# warm_floor.net
KiCad netlist of a schematic drawn in EAGLE
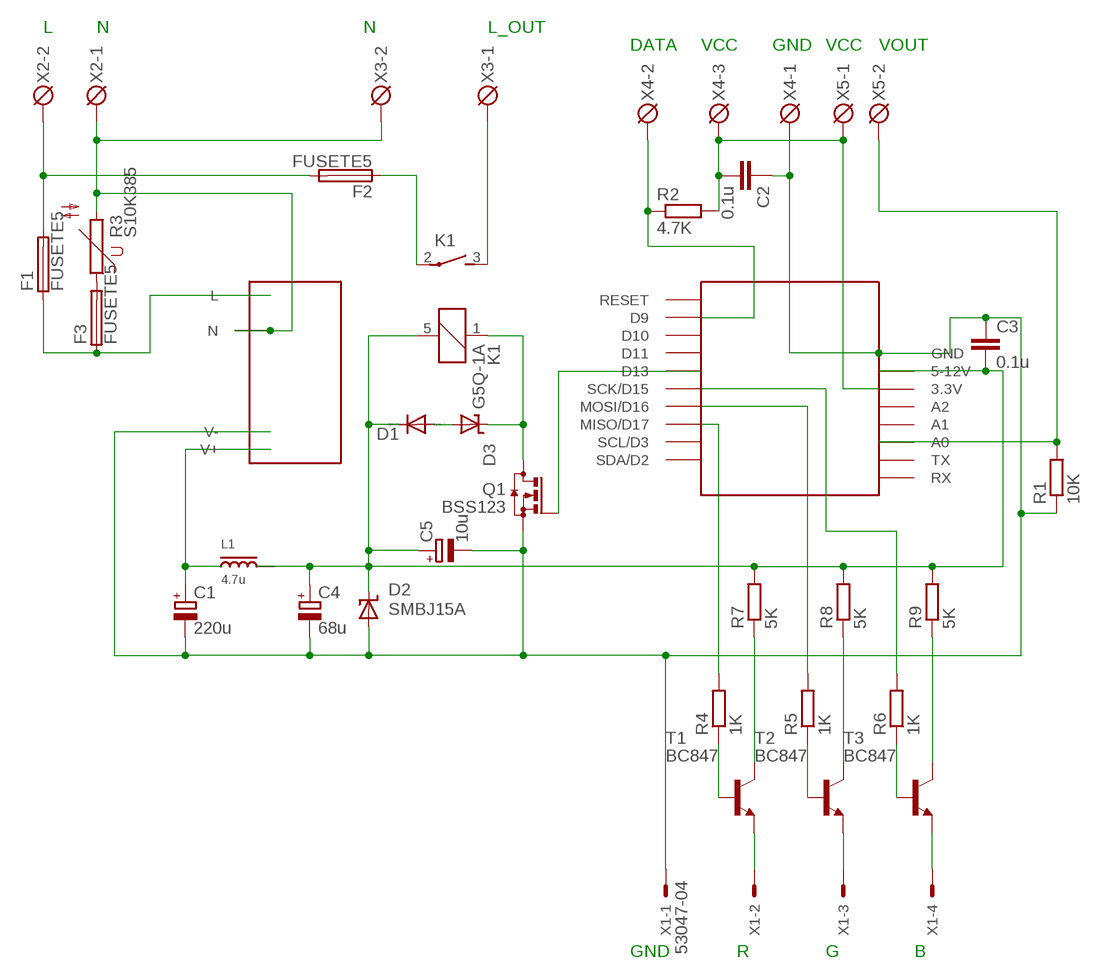
[diagram p0: schematic, sheet 1]

(export (version "E")
  (design (tool "Eeschema 10.0.6"))
  (components
    (comp (ref "C1")
      (value "220u")
      (footprint "eagle-import:E2,5-6")
      (libsource (lib "eagle-import") (part "CPOL-EUE2.5-6"))
    )
    (comp (ref "C2")
      (value "0.1u")
      (footprint "eagle-import:C0805")
      (libsource (lib "eagle-import") (part "C-EUC0805"))
    )
    (comp (ref "C3")
      (value "0.1u")
      (footprint "eagle-import:C0805")
      (libsource (lib "eagle-import") (part "C-EUC0805"))
    )
    (comp (ref "C4")
      (value "68u")
      (footprint "eagle-import:E2,5-7")
      (libsource (lib "eagle-import") (part "CPOL-EUE2.5-7"))
    )
    (comp (ref "C5")
      (value "10u")
      (footprint "eagle-import:E2,5-6")
      (libsource (lib "eagle-import") (part "CPOL-EUE2.5-6"))
    )
    (comp (ref "D1")
      (value "DIODE-SOD123")
      (footprint "eagle-import:SOD123")
      (libsource (lib "eagle-import") (part "DIODE-SOD123"))
    )
    (comp (ref "D2")
      (value "SMBJ15A")
      (footprint "eagle-import:SMBJ")
      (libsource (lib "eagle-import") (part "SUPPRESSOR-SMBJ"))
    )
    (comp (ref "D3")
      (value "SUPPRESSOR-SMBJ")
      (footprint "eagle-import:SMBJ")
      (libsource (lib "eagle-import") (part "SUPPRESSOR-SMBJ"))
    )
    (comp (ref "F1")
      (value "FUSETE5")
      (footprint "eagle-import:TE5")
      (libsource (lib "eagle-import") (part "FUSETE5"))
    )
    (comp (ref "F2")
      (value "FUSETE5")
      (footprint "eagle-import:TE5")
      (libsource (lib "eagle-import") (part "FUSETE5"))
    )
    (comp (ref "F3")
      (value "FUSETE5")
      (footprint "eagle-import:TE5")
      (libsource (lib "eagle-import") (part "FUSETE5"))
    )
    (comp (ref "K1")
      (value "G5Q-1A")
      (footprint "eagle-import:G5Q-1A")
      (libsource (lib "eagle-import") (part "G5Q-1A"))
    )
    (comp (ref "L1")
      (value "4.7u")
      (footprint "eagle-import:LQH43")
      (libsource (lib "eagle-import") (part "LQH43"))
    )
    (comp (ref "Q1")
      (value "BSS123")
      (footprint "eagle-import:SOT23")
      (libsource (lib "eagle-import") (part "BSS123"))
    )
    (comp (ref "R1")
      (value "10K")
      (footprint "eagle-import:R0805")
      (libsource (lib "eagle-import") (part "R-EU_R0805"))
    )
    (comp (ref "R2")
      (value "4.7K")
      (footprint "eagle-import:R0805")
      (libsource (lib "eagle-import") (part "R-EU_R0805"))
    )
    (comp (ref "R3")
      (value "S10K385")
      (footprint "eagle-import:S10K385")
      (libsource (lib "eagle-import") (part "S10K385"))
    )
    (comp (ref "R4")
      (value "1K")
      (footprint "eagle-import:R0805")
      (libsource (lib "eagle-import") (part "resistor_348_R-EU_R0805"))
    )
    (comp (ref "R5")
      (value "1K")
      (footprint "eagle-import:R0805")
      (libsource (lib "eagle-import") (part "resistor_348_R-EU_R0805"))
    )
    (comp (ref "R6")
      (value "1K")
      (footprint "eagle-import:R0805")
      (libsource (lib "eagle-import") (part "resistor_348_R-EU_R0805"))
    )
    (comp (ref "R7")
      (value "5K")
      (footprint "eagle-import:R0805")
      (libsource (lib "eagle-import") (part "resistor_348_R-EU_R0805"))
    )
    (comp (ref "R8")
      (value "5K")
      (footprint "eagle-import:R0805")
      (libsource (lib "eagle-import") (part "resistor_348_R-EU_R0805"))
    )
    (comp (ref "R9")
      (value "5K")
      (footprint "eagle-import:R0805")
      (libsource (lib "eagle-import") (part "resistor_348_R-EU_R0805"))
    )
    (comp (ref "T1")
      (value "BC847")
      (footprint "eagle-import:SOT23")
      (libsource (lib "eagle-import") (part "BC847"))
    )
    (comp (ref "T2")
      (value "BC847")
      (footprint "eagle-import:SOT23")
      (libsource (lib "eagle-import") (part "BC847"))
    )
    (comp (ref "T3")
      (value "BC847")
      (footprint "eagle-import:SOT23")
      (libsource (lib "eagle-import") (part "BC847"))
    )
    (comp (ref "U$1")
      (value "SMARTBRICK")
      (footprint "eagle-import:SMARTBRICK")
      (libsource (lib "eagle-import") (part "SMARTBRICK"))
    )
    (comp (ref "U$2")
      (value "NA01/02-T2SXX")
      (footprint "eagle-import:NA01_02-T2SXX")
      (libsource (lib "eagle-import") (part "NA01/02-T2SXX"))
    )
    (comp (ref "X1")
      (value "53047-04")
      (footprint "eagle-import:53047-04")
      (fields (field (name "MF") "WALDOM/MOLEX") (field (name "MPN") "53047-0410"))
      (libsource (lib "eagle-import") (part "53?-04047"))
    )
    (comp (ref "X2")
      (value "DG3XX-025.0")
      (footprint "eagle-import:DG300-5.0-02P")
      (libsource (lib "eagle-import") (part "DG3XX-025.0"))
    )
    (comp (ref "X3")
      (value "DG3XX-025.0")
      (footprint "eagle-import:DG300-5.0-02P")
      (libsource (lib "eagle-import") (part "DG3XX-025.0"))
    )
    (comp (ref "X4")
      (value "DG3XX-03-3.5")
      (footprint "eagle-import:DG350-3.5-03P")
      (libsource (lib "eagle-import") (part "DG3XX-03-3.5"))
    )
    (comp (ref "X5")
      (value "DG3XX-02-3.5")
      (footprint "eagle-import:DG350-3.5-02P")
      (libsource (lib "eagle-import") (part "DG3XX-02-3.5"))
    )
  )
  (nets
    (net (code "1") (name "Net-(C1-Pad+)") (class "Default")
      (node (ref "C1") (pin "+") (pinfunction "+_+") (pintype "passive"))
      (node (ref "L1") (pin "P$1") (pinfunction "P$1_P$1") (pintype "bidirectional"))
      (node (ref "U$2") (pin "V+") (pinfunction "V+_V+") (pintype "output"))
    )
    (net (code "2") (name "Net-(D1-PadA)") (class "Default")
      (node (ref "D1") (pin "A") (pinfunction "A_A") (pintype "passive"))
      (node (ref "D3") (pin "A") (pinfunction "A_A") (pintype "passive"))
    )
    (net (code "3") (name "Net-(F1-Pad1)") (class "Default")
      (node (ref "F1") (pin "1") (pinfunction "1_1") (pintype "passive"))
      (node (ref "F3") (pin "1") (pinfunction "1_1") (pintype "passive"))
      (node (ref "U$2") (pin "L") (pinfunction "L_L") (pintype "input"))
    )
    (net (code "4") (name "Net-(F3-Pad2)") (class "Default")
      (node (ref "F3") (pin "2") (pinfunction "2_2") (pintype "passive"))
      (node (ref "R3") (pin "1") (pinfunction "1_1") (pintype "passive"))
    )
    (net (code "5") (name "Net-(K1A-2)") (class "Default")
      (node (ref "C3") (pin "2") (pinfunction "2_2") (pintype "passive"))
      (node (ref "C4") (pin "+") (pinfunction "+_+") (pintype "passive"))
      (node (ref "C5") (pin "+") (pinfunction "+_+") (pintype "passive"))
      (node (ref "D1") (pin "C") (pinfunction "C_C") (pintype "passive"))
      (node (ref "D2") (pin "C") (pinfunction "C_C") (pintype "passive"))
      (node (ref "K1") (pin "5") (pinfunction "2_5") (pintype "passive"))
      (node (ref "L1") (pin "P$2") (pinfunction "P$2_P$2") (pintype "bidirectional"))
      (node (ref "R7") (pin "2") (pinfunction "2_2") (pintype "passive"))
      (node (ref "R8") (pin "2") (pinfunction "2_2") (pintype "passive"))
      (node (ref "R9") (pin "2") (pinfunction "2_2") (pintype "passive"))
      (node (ref "U$1") (pin "VIN") (pinfunction "5-12V_VIN") (pintype "input"))
    )
    (net (code "6") (name "Net-(K1B-P)") (class "Default")
      (node (ref "F2") (pin "1") (pinfunction "1_1") (pintype "passive"))
      (node (ref "K1") (pin "2") (pinfunction "P_2") (pintype "passive"))
    )
    (net (code "7") (name "Net-(K1B-S)") (class "Default")
      (node (ref "K1") (pin "3") (pinfunction "S_3") (pintype "passive"))
      (node (ref "X3") (pin "1") (pinfunction "KL_1") (pintype "passive"))
    )
    (net (code "8") (name "Net-(Q1-D)") (class "Default")
      (node (ref "D3") (pin "C") (pinfunction "C_C") (pintype "passive"))
      (node (ref "K1") (pin "1") (pinfunction "1_1") (pintype "passive"))
      (node (ref "Q1") (pin "3") (pinfunction "D_3") (pintype "passive"))
    )
    (net (code "9") (name "Net-(Q1-G)") (class "Default")
      (node (ref "Q1") (pin "1") (pinfunction "G_1") (pintype "passive"))
      (node (ref "U$1") (pin "D13") (pinfunction "D13_D13") (pintype "bidirectional"))
    )
    (net (code "10") (name "Net-(Q1-S)") (class "Default")
      (node (ref "C1") (pin "-") (pinfunction "-_-") (pintype "passive"))
      (node (ref "C2") (pin "1") (pinfunction "1_1") (pintype "passive"))
      (node (ref "C3") (pin "1") (pinfunction "1_1") (pintype "passive"))
      (node (ref "C4") (pin "-") (pinfunction "-_-") (pintype "passive"))
      (node (ref "C5") (pin "-") (pinfunction "-_-") (pintype "passive"))
      (node (ref "D2") (pin "A") (pinfunction "A_A") (pintype "passive"))
      (node (ref "Q1") (pin "2") (pinfunction "S_2") (pintype "passive"))
      (node (ref "R1") (pin "1") (pinfunction "1_1") (pintype "passive"))
      (node (ref "U$1") (pin "GND") (pinfunction "GND_GND") (pintype "power_in"))
      (node (ref "U$2") (pin "V-") (pinfunction "V-_V-") (pintype "output"))
      (node (ref "X1") (pin "1") (pinfunction "S_1") (pintype "passive"))
      (node (ref "X4") (pin "1") (pinfunction "KL_1") (pintype "passive"))
    )
    (net (code "11") (name "Net-(R4-Pad2)") (class "Default")
      (node (ref "R4") (pin "2") (pinfunction "2_2") (pintype "passive"))
      (node (ref "U$1") (pin "MISO/D17") (pinfunction "MISO/D17_MISO/D17") (pintype "bidirectional"))
    )
    (net (code "12") (name "Net-(R5-Pad2)") (class "Default")
      (node (ref "R5") (pin "2") (pinfunction "2_2") (pintype "passive"))
      (node (ref "U$1") (pin "MOSI/D16") (pinfunction "MOSI/D16_MOSI/D16") (pintype "bidirectional"))
    )
    (net (code "13") (name "Net-(R6-Pad2)") (class "Default")
      (node (ref "R6") (pin "2") (pinfunction "2_2") (pintype "passive"))
      (node (ref "U$1") (pin "SCK/D15") (pinfunction "SCK/D15_SCK/D15") (pintype "bidirectional"))
    )
    (net (code "14") (name "Net-(T1-B)") (class "Default")
      (node (ref "R4") (pin "1") (pinfunction "1_1") (pintype "passive"))
      (node (ref "T1") (pin "1") (pinfunction "B_1") (pintype "passive"))
    )
    (net (code "15") (name "Net-(T1-C)") (class "Default")
      (node (ref "R7") (pin "1") (pinfunction "1_1") (pintype "passive"))
      (node (ref "T1") (pin "3") (pinfunction "C_3") (pintype "passive"))
    )
    (net (code "16") (name "Net-(T1-E)") (class "Default")
      (node (ref "T1") (pin "2") (pinfunction "E_2") (pintype "passive"))
      (node (ref "X1") (pin "2") (pinfunction "S_2") (pintype "passive"))
    )
    (net (code "17") (name "Net-(T2-B)") (class "Default")
      (node (ref "R5") (pin "1") (pinfunction "1_1") (pintype "passive"))
      (node (ref "T2") (pin "1") (pinfunction "B_1") (pintype "passive"))
    )
    (net (code "18") (name "Net-(T2-C)") (class "Default")
      (node (ref "R8") (pin "1") (pinfunction "1_1") (pintype "passive"))
      (node (ref "T2") (pin "3") (pinfunction "C_3") (pintype "passive"))
    )
    (net (code "19") (name "Net-(T2-E)") (class "Default")
      (node (ref "T2") (pin "2") (pinfunction "E_2") (pintype "passive"))
      (node (ref "X1") (pin "3") (pinfunction "S_3") (pintype "passive"))
    )
    (net (code "20") (name "Net-(T3-B)") (class "Default")
      (node (ref "R6") (pin "1") (pinfunction "1_1") (pintype "passive"))
      (node (ref "T3") (pin "1") (pinfunction "B_1") (pintype "passive"))
    )
    (net (code "21") (name "Net-(T3-C)") (class "Default")
      (node (ref "R9") (pin "1") (pinfunction "1_1") (pintype "passive"))
      (node (ref "T3") (pin "3") (pinfunction "C_3") (pintype "passive"))
    )
    (net (code "22") (name "Net-(T3-E)") (class "Default")
      (node (ref "T3") (pin "2") (pinfunction "E_2") (pintype "passive"))
      (node (ref "X1") (pin "4") (pinfunction "S_4") (pintype "passive"))
    )
    (net (code "23") (name "Net-(X2A-KL)") (class "Default")
      (node (ref "R3") (pin "2") (pinfunction "2_2") (pintype "passive"))
      (node (ref "U$2") (pin "N") (pinfunction "N_N") (pintype "input"))
      (node (ref "X2") (pin "1") (pinfunction "KL_1") (pintype "passive"))
      (node (ref "X3") (pin "2") (pinfunction "KL_2") (pintype "passive"))
    )
    (net (code "24") (name "Net-(X2B-KL)") (class "Default")
      (node (ref "F1") (pin "2") (pinfunction "2_2") (pintype "passive"))
      (node (ref "F2") (pin "2") (pinfunction "2_2") (pintype "passive"))
      (node (ref "X2") (pin "2") (pinfunction "KL_2") (pintype "passive"))
    )
    (net (code "25") (name "Net-(X4B-KL)") (class "Default")
      (node (ref "R2") (pin "1") (pinfunction "1_1") (pintype "passive"))
      (node (ref "U$1") (pin "D9") (pinfunction "D9_D9") (pintype "bidirectional"))
      (node (ref "X4") (pin "2") (pinfunction "KL_2") (pintype "passive"))
    )
    (net (code "26") (name "Net-(X4C-KL)") (class "Default")
      (node (ref "C2") (pin "2") (pinfunction "2_2") (pintype "passive"))
      (node (ref "R2") (pin "2") (pinfunction "2_2") (pintype "passive"))
      (node (ref "U$1") (pin "3.3V") (pinfunction "3.3V_3.3V") (pintype "power_in"))
      (node (ref "X4") (pin "3") (pinfunction "KL_3") (pintype "passive"))
      (node (ref "X5") (pin "1") (pinfunction "KL_1") (pintype "passive"))
    )
    (net (code "27") (name "Net-(X5B-KL)") (class "Default")
      (node (ref "R1") (pin "2") (pinfunction "2_2") (pintype "passive"))
      (node (ref "U$1") (pin "A0") (pinfunction "A0_A0") (pintype "bidirectional"))
      (node (ref "X5") (pin "2") (pinfunction "KL_2") (pintype "passive"))
    )
    (net (code "28") (name "unconnected-(U$1-PadA1)") (class "Default")
      (node (ref "U$1") (pin "A1") (pinfunction "A1_A1") (pintype "bidirectional"))
    )
    (net (code "29") (name "unconnected-(U$1-PadA2)") (class "Default")
      (node (ref "U$1") (pin "A2") (pinfunction "A2_A2") (pintype "bidirectional"))
    )
    (net (code "30") (name "unconnected-(U$1-PadD10)") (class "Default")
      (node (ref "U$1") (pin "D10") (pinfunction "D10_D10") (pintype "bidirectional"))
    )
    (net (code "31") (name "unconnected-(U$1-PadD11)") (class "Default")
      (node (ref "U$1") (pin "D11") (pinfunction "D11_D11") (pintype "bidirectional"))
    )
    (net (code "32") (name "unconnected-(U$1-PadRESET)") (class "Default")
      (node (ref "U$1") (pin "RESET") (pinfunction "RESET_RESET") (pintype "bidirectional"))
    )
    (net (code "33") (name "unconnected-(U$1-PadRX)") (class "Default")
      (node (ref "U$1") (pin "RX") (pinfunction "RX_RX") (pintype "bidirectional"))
    )
    (net (code "34") (name "unconnected-(U$1-PadSCL{slash}D3)") (class "Default")
      (node (ref "U$1") (pin "SCL/D3") (pinfunction "SCL/D3_SCL/D3") (pintype "bidirectional"))
    )
    (net (code "35") (name "unconnected-(U$1-PadSDA{slash}D2)") (class "Default")
      (node (ref "U$1") (pin "SDA/D2") (pinfunction "SDA/D2_SDA/D2") (pintype "bidirectional"))
    )
    (net (code "36") (name "unconnected-(U$1-PadTX)") (class "Default")
      (node (ref "U$1") (pin "TX") (pinfunction "TX_TX") (pintype "bidirectional"))
    )
  )
)
